# CR78-SD.net
KiCad netlist of a schematic drawn in EAGLE
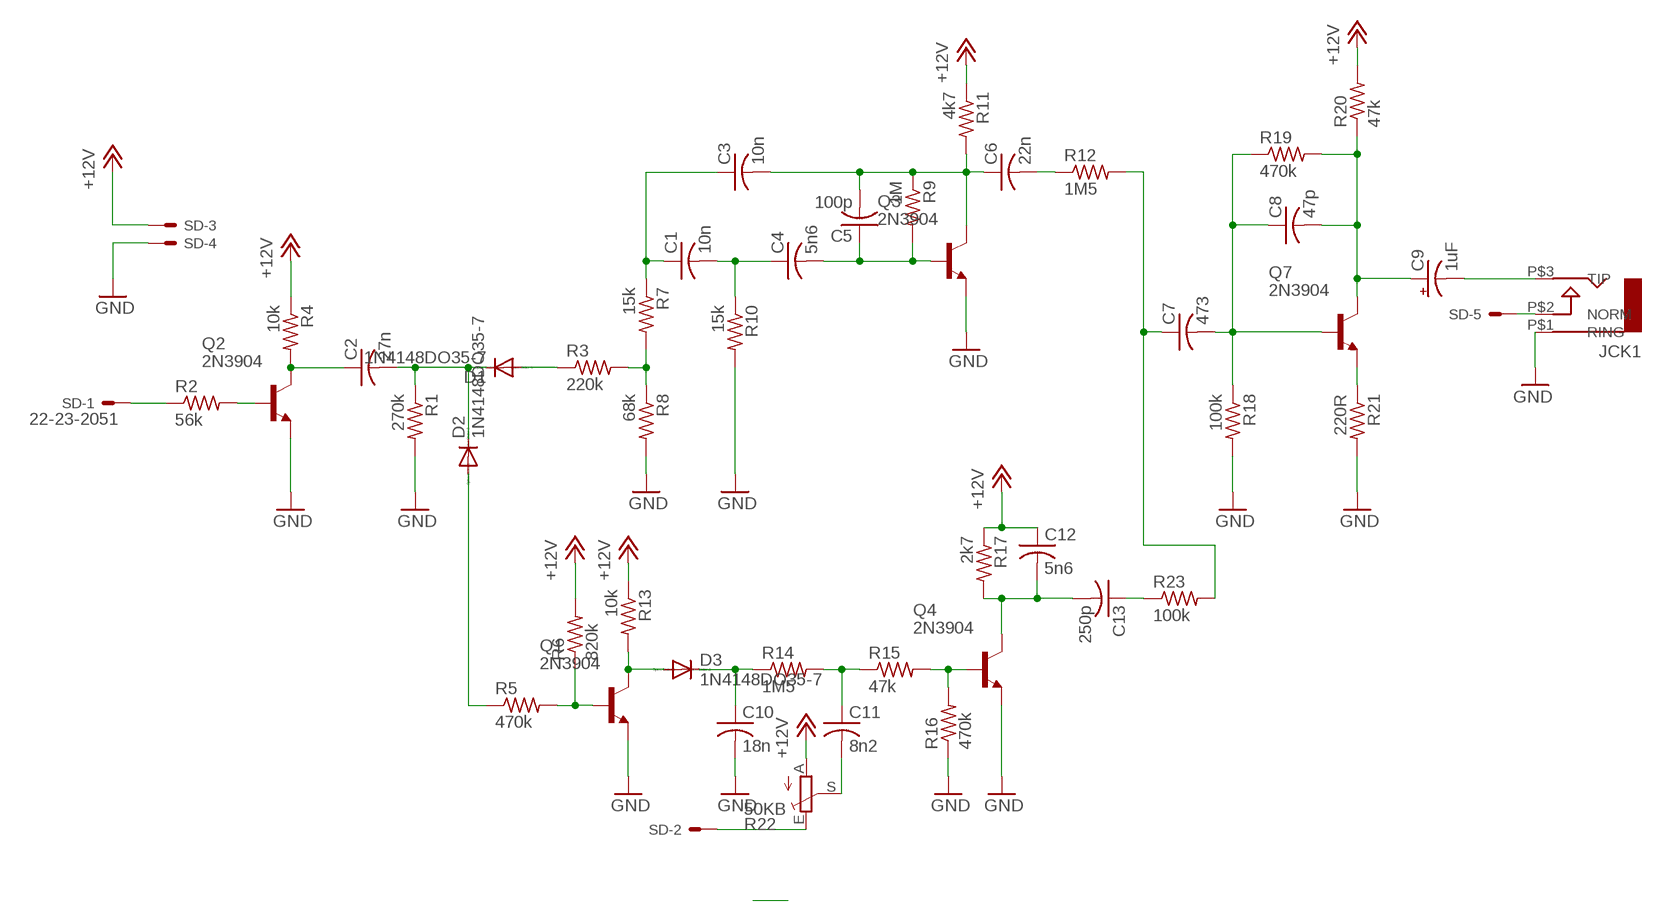
[diagram p0: schematic, sheet 1]

(export (version "E")
  (design (tool "Eeschema 10.0.6"))
  (components
    (comp (ref "C1")
      (value "10n")
      (footprint "eagle-import:C050-025X075")
      (libsource (lib "eagle-import") (part "C-US050-025X075"))
    )
    (comp (ref "C2")
      (value "27n")
      (footprint "eagle-import:C050-025X075")
      (libsource (lib "eagle-import") (part "C-US050-025X075"))
    )
    (comp (ref "C3")
      (value "10n")
      (footprint "eagle-import:C050-025X075")
      (libsource (lib "eagle-import") (part "C-US050-025X075"))
    )
    (comp (ref "C4")
      (value "5n6")
      (footprint "eagle-import:C050-025X075")
      (libsource (lib "eagle-import") (part "C-US050-025X075"))
    )
    (comp (ref "C5")
      (value "100p")
      (footprint "eagle-import:C050-025X075")
      (libsource (lib "eagle-import") (part "C-US050-025X075"))
    )
    (comp (ref "C6")
      (value "22n")
      (footprint "eagle-import:C050-025X075")
      (libsource (lib "eagle-import") (part "C-US050-025X075"))
    )
    (comp (ref "C7")
      (value "473")
      (footprint "eagle-import:C050-025X075")
      (libsource (lib "eagle-import") (part "C-US050-025X075"))
    )
    (comp (ref "C8")
      (value "47p")
      (footprint "eagle-import:C050-025X075")
      (libsource (lib "eagle-import") (part "C-US050-025X075"))
    )
    (comp (ref "C9")
      (value "1uF")
      (footprint "eagle-import:B45181B")
      (libsource (lib "eagle-import") (part "CPOL-USB45181B"))
    )
    (comp (ref "C10")
      (value "18n")
      (footprint "eagle-import:C050-025X075")
      (libsource (lib "eagle-import") (part "C-US050-025X075"))
    )
    (comp (ref "C11")
      (value "8n2")
      (footprint "eagle-import:C050-025X075")
      (libsource (lib "eagle-import") (part "C-US050-025X075"))
    )
    (comp (ref "C12")
      (value "5n6")
      (footprint "eagle-import:C050-025X075")
      (libsource (lib "eagle-import") (part "C-US050-025X075"))
    )
    (comp (ref "C13")
      (value "250p")
      (footprint "eagle-import:C050-025X075")
      (libsource (lib "eagle-import") (part "C-US050-025X075"))
    )
    (comp (ref "D1")
      (value "1N4148DO35-7")
      (footprint "eagle-import:DO35-7")
      (libsource (lib "eagle-import") (part "1N4148DO35-7"))
    )
    (comp (ref "D2")
      (value "1N4148DO35-7")
      (footprint "eagle-import:DO35-7")
      (libsource (lib "eagle-import") (part "1N4148DO35-7"))
    )
    (comp (ref "D3")
      (value "1N4148DO35-7")
      (footprint "eagle-import:DO35-7")
      (libsource (lib "eagle-import") (part "1N4148DO35-7"))
    )
    (comp (ref "JCK1")
      (value "AUDIO-JACK")
      (footprint "eagle-import:ERTHENVAR-JACK-90DEG")
      (libsource (lib "eagle-import") (part "AUDIO-JACK"))
    )
    (comp (ref "Q1")
      (value "2N3904")
      (footprint "eagle-import:TO92")
      (libsource (lib "eagle-import") (part "2N3904"))
    )
    (comp (ref "Q2")
      (value "2N3904")
      (footprint "eagle-import:TO92")
      (libsource (lib "eagle-import") (part "2N3904"))
    )
    (comp (ref "Q3")
      (value "2N3904")
      (footprint "eagle-import:TO92")
      (libsource (lib "eagle-import") (part "2N3904"))
    )
    (comp (ref "Q4")
      (value "2N3904")
      (footprint "eagle-import:TO92")
      (libsource (lib "eagle-import") (part "2N3904"))
    )
    (comp (ref "Q7")
      (value "2N3904")
      (footprint "eagle-import:TO92")
      (libsource (lib "eagle-import") (part "2N3904"))
    )
    (comp (ref "R1")
      (value "270k")
      (footprint "eagle-import:0207_7")
      (libsource (lib "eagle-import") (part "R-US_0207/7"))
    )
    (comp (ref "R2")
      (value "56k")
      (footprint "eagle-import:0207_7")
      (libsource (lib "eagle-import") (part "R-US_0207/7"))
    )
    (comp (ref "R3")
      (value "220k")
      (footprint "eagle-import:0207_7")
      (libsource (lib "eagle-import") (part "R-US_0207/7"))
    )
    (comp (ref "R4")
      (value "10k")
      (footprint "eagle-import:0207_7")
      (libsource (lib "eagle-import") (part "R-US_0207/7"))
    )
    (comp (ref "R5")
      (value "470k")
      (footprint "eagle-import:0207_7")
      (libsource (lib "eagle-import") (part "R-US_0207/7"))
    )
    (comp (ref "R6")
      (value "820k")
      (footprint "eagle-import:0207_7")
      (libsource (lib "eagle-import") (part "R-US_0207/7"))
    )
    (comp (ref "R7")
      (value "15k")
      (footprint "eagle-import:0207_7")
      (libsource (lib "eagle-import") (part "R-US_0207/7"))
    )
    (comp (ref "R8")
      (value "68k")
      (footprint "eagle-import:0207_7")
      (libsource (lib "eagle-import") (part "R-US_0207/7"))
    )
    (comp (ref "R9")
      (value "1M")
      (footprint "eagle-import:0207_7")
      (libsource (lib "eagle-import") (part "R-US_0207/7"))
    )
    (comp (ref "R10")
      (value "15k")
      (footprint "eagle-import:0207_7")
      (libsource (lib "eagle-import") (part "R-US_0207/7"))
    )
    (comp (ref "R11")
      (value "4k7")
      (footprint "eagle-import:0207_7")
      (libsource (lib "eagle-import") (part "R-US_0207/7"))
    )
    (comp (ref "R12")
      (value "1M5")
      (footprint "eagle-import:0207_7")
      (libsource (lib "eagle-import") (part "R-US_0207/7"))
    )
    (comp (ref "R13")
      (value "10k")
      (footprint "eagle-import:0207_7")
      (libsource (lib "eagle-import") (part "R-US_0207/7"))
    )
    (comp (ref "R14")
      (value "1M5")
      (footprint "eagle-import:0207_7")
      (libsource (lib "eagle-import") (part "R-US_0207/7"))
    )
    (comp (ref "R15")
      (value "47k")
      (footprint "eagle-import:0207_7")
      (libsource (lib "eagle-import") (part "R-US_0207/7"))
    )
    (comp (ref "R16")
      (value "470k")
      (footprint "eagle-import:0207_7")
      (libsource (lib "eagle-import") (part "R-US_0207/7"))
    )
    (comp (ref "R17")
      (value "2k7")
      (footprint "eagle-import:0207_7")
      (libsource (lib "eagle-import") (part "R-US_0207/7"))
    )
    (comp (ref "R18")
      (value "100k")
      (footprint "eagle-import:0207_7")
      (libsource (lib "eagle-import") (part "R-US_0207/7"))
    )
    (comp (ref "R19")
      (value "470k")
      (footprint "eagle-import:0207_7")
      (libsource (lib "eagle-import") (part "R-US_0207/7"))
    )
    (comp (ref "R20")
      (value "47k")
      (footprint "eagle-import:0207_7")
      (libsource (lib "eagle-import") (part "R-US_0207/7"))
    )
    (comp (ref "R21")
      (value "220R")
      (footprint "eagle-import:0207_7")
      (libsource (lib "eagle-import") (part "R-US_0207/7"))
    )
    (comp (ref "R22")
      (value "50KB")
      (footprint "eagle-import:B64Y")
      (libsource (lib "eagle-import") (part "TRIM_EU-B64Y"))
    )
    (comp (ref "R23")
      (value "100k")
      (footprint "eagle-import:0207_7")
      (libsource (lib "eagle-import") (part "R-US_0207/7"))
    )
    (comp (ref "SD")
      (value "22-23-2051")
      (footprint "eagle-import:22-23-2051")
      (fields (field (name "MF") "MOLEX"))
      (libsource (lib "eagle-import") (part "22-23-2051"))
    )
  )
  (nets
    (net (code "1") (name "+12V") (class "Default")
      (node (ref "C12") (pin "1") (pinfunction "1_1") (pintype "passive"))
      (node (ref "R11") (pin "1") (pinfunction "1_1") (pintype "passive"))
      (node (ref "R13") (pin "1") (pinfunction "1_1") (pintype "passive"))
      (node (ref "R17") (pin "1") (pinfunction "1_1") (pintype "passive"))
      (node (ref "R20") (pin "2") (pinfunction "2_2") (pintype "passive"))
      (node (ref "R22") (pin "A") (pinfunction "A_A") (pintype "passive"))
      (node (ref "R4") (pin "1") (pinfunction "1_1") (pintype "passive"))
      (node (ref "R6") (pin "2") (pinfunction "2_2") (pintype "passive"))
      (node (ref "SD") (pin "3") (pinfunction "S_3") (pintype "passive"))
    )
    (net (code "2") (name "GND") (class "Default")
      (node (ref "C10") (pin "2") (pinfunction "2_2") (pintype "passive"))
      (node (ref "JCK1") (pin "P$1") (pinfunction "RING_P$1") (pintype "bidirectional"))
      (node (ref "Q1") (pin "3") (pinfunction "E_3") (pintype "passive"))
      (node (ref "Q2") (pin "3") (pinfunction "E_3") (pintype "passive"))
      (node (ref "Q3") (pin "3") (pinfunction "E_3") (pintype "passive"))
      (node (ref "Q4") (pin "3") (pinfunction "E_3") (pintype "passive"))
      (node (ref "R1") (pin "2") (pinfunction "2_2") (pintype "passive"))
      (node (ref "R10") (pin "2") (pinfunction "2_2") (pintype "passive"))
      (node (ref "R16") (pin "1") (pinfunction "1_1") (pintype "passive"))
      (node (ref "R18") (pin "2") (pinfunction "2_2") (pintype "passive"))
      (node (ref "R21") (pin "2") (pinfunction "2_2") (pintype "passive"))
      (node (ref "R8") (pin "2") (pinfunction "2_2") (pintype "passive"))
      (node (ref "SD") (pin "4") (pinfunction "S_4") (pintype "passive"))
    )
    (net (code "3") (name "Net-(C1-Pad1)") (class "Default")
      (node (ref "C1") (pin "1") (pinfunction "1_1") (pintype "passive"))
      (node (ref "C3") (pin "1") (pinfunction "1_1") (pintype "passive"))
      (node (ref "R7") (pin "1") (pinfunction "1_1") (pintype "passive"))
    )
    (net (code "4") (name "Net-(C1-Pad2)") (class "Default")
      (node (ref "C1") (pin "2") (pinfunction "2_2") (pintype "passive"))
      (node (ref "C4") (pin "1") (pinfunction "1_1") (pintype "passive"))
      (node (ref "R10") (pin "1") (pinfunction "1_1") (pintype "passive"))
    )
    (net (code "5") (name "Net-(C2-Pad2)") (class "Default")
      (node (ref "C2") (pin "2") (pinfunction "2_2") (pintype "passive"))
      (node (ref "D1") (pin "C") (pinfunction "C_C") (pintype "passive"))
      (node (ref "D2") (pin "C") (pinfunction "C_C") (pintype "passive"))
      (node (ref "R1") (pin "1") (pinfunction "1_1") (pintype "passive"))
    )
    (net (code "6") (name "Net-(C6-Pad2)") (class "Default")
      (node (ref "C6") (pin "2") (pinfunction "2_2") (pintype "passive"))
      (node (ref "R12") (pin "1") (pinfunction "1_1") (pintype "passive"))
    )
    (net (code "7") (name "Net-(C7-Pad1)") (class "Default")
      (node (ref "C7") (pin "1") (pinfunction "1_1") (pintype "passive"))
      (node (ref "R12") (pin "2") (pinfunction "2_2") (pintype "passive"))
      (node (ref "R23") (pin "2") (pinfunction "2_2") (pintype "passive"))
    )
    (net (code "8") (name "Net-(C10-Pad1)") (class "Default")
      (node (ref "C10") (pin "1") (pinfunction "1_1") (pintype "passive"))
      (node (ref "D3") (pin "C") (pinfunction "C_C") (pintype "passive"))
      (node (ref "R14") (pin "1") (pinfunction "1_1") (pintype "passive"))
    )
    (net (code "9") (name "Net-(C11-Pad1)") (class "Default")
      (node (ref "C11") (pin "1") (pinfunction "1_1") (pintype "passive"))
      (node (ref "R14") (pin "2") (pinfunction "2_2") (pintype "passive"))
      (node (ref "R15") (pin "1") (pinfunction "1_1") (pintype "passive"))
    )
    (net (code "10") (name "Net-(C11-Pad2)") (class "Default")
      (node (ref "C11") (pin "2") (pinfunction "2_2") (pintype "passive"))
      (node (ref "R22") (pin "S") (pinfunction "S_S") (pintype "passive"))
    )
    (net (code "11") (name "Net-(C13-Pad1)") (class "Default")
      (node (ref "C13") (pin "1") (pinfunction "1_1") (pintype "passive"))
      (node (ref "R23") (pin "1") (pinfunction "1_1") (pintype "passive"))
    )
    (net (code "12") (name "Net-(D1-PadA)") (class "Default")
      (node (ref "D1") (pin "A") (pinfunction "A_A") (pintype "passive"))
      (node (ref "R3") (pin "1") (pinfunction "1_1") (pintype "passive"))
    )
    (net (code "13") (name "Net-(D2-PadA)") (class "Default")
      (node (ref "D2") (pin "A") (pinfunction "A_A") (pintype "passive"))
      (node (ref "R5") (pin "1") (pinfunction "1_1") (pintype "passive"))
    )
    (net (code "14") (name "Net-(JCK1-NORM)") (class "Default")
      (node (ref "JCK1") (pin "P$2") (pinfunction "NORM_P$2") (pintype "bidirectional"))
      (node (ref "SD") (pin "5") (pinfunction "S_5") (pintype "passive"))
    )
    (net (code "15") (name "Net-(JCK1-TIP)") (class "Default")
      (node (ref "C9") (pin "-") (pinfunction "-_-") (pintype "passive"))
      (node (ref "JCK1") (pin "P$3") (pinfunction "TIP_P$3") (pintype "bidirectional"))
    )
    (net (code "16") (name "Net-(Q1-B)") (class "Default")
      (node (ref "Q1") (pin "2") (pinfunction "B_2") (pintype "passive"))
      (node (ref "R5") (pin "2") (pinfunction "2_2") (pintype "passive"))
      (node (ref "R6") (pin "1") (pinfunction "1_1") (pintype "passive"))
    )
    (net (code "17") (name "Net-(Q1-C)") (class "Default")
      (node (ref "D3") (pin "A") (pinfunction "A_A") (pintype "passive"))
      (node (ref "Q1") (pin "1") (pinfunction "C_1") (pintype "passive"))
      (node (ref "R13") (pin "2") (pinfunction "2_2") (pintype "passive"))
    )
    (net (code "18") (name "Net-(Q2-B)") (class "Default")
      (node (ref "Q2") (pin "2") (pinfunction "B_2") (pintype "passive"))
      (node (ref "R2") (pin "2") (pinfunction "2_2") (pintype "passive"))
    )
    (net (code "19") (name "Net-(Q2-C)") (class "Default")
      (node (ref "C2") (pin "1") (pinfunction "1_1") (pintype "passive"))
      (node (ref "Q2") (pin "1") (pinfunction "C_1") (pintype "passive"))
      (node (ref "R4") (pin "2") (pinfunction "2_2") (pintype "passive"))
    )
    (net (code "20") (name "Net-(Q3-B)") (class "Default")
      (node (ref "C4") (pin "2") (pinfunction "2_2") (pintype "passive"))
      (node (ref "C5") (pin "1") (pinfunction "1_1") (pintype "passive"))
      (node (ref "Q3") (pin "2") (pinfunction "B_2") (pintype "passive"))
      (node (ref "R9") (pin "2") (pinfunction "2_2") (pintype "passive"))
    )
    (net (code "21") (name "Net-(Q3-C)") (class "Default")
      (node (ref "C3") (pin "2") (pinfunction "2_2") (pintype "passive"))
      (node (ref "C5") (pin "2") (pinfunction "2_2") (pintype "passive"))
      (node (ref "C6") (pin "1") (pinfunction "1_1") (pintype "passive"))
      (node (ref "Q3") (pin "1") (pinfunction "C_1") (pintype "passive"))
      (node (ref "R11") (pin "2") (pinfunction "2_2") (pintype "passive"))
      (node (ref "R9") (pin "1") (pinfunction "1_1") (pintype "passive"))
    )
    (net (code "22") (name "Net-(Q4-B)") (class "Default")
      (node (ref "Q4") (pin "2") (pinfunction "B_2") (pintype "passive"))
      (node (ref "R15") (pin "2") (pinfunction "2_2") (pintype "passive"))
      (node (ref "R16") (pin "2") (pinfunction "2_2") (pintype "passive"))
    )
    (net (code "23") (name "Net-(Q4-C)") (class "Default")
      (node (ref "C12") (pin "2") (pinfunction "2_2") (pintype "passive"))
      (node (ref "C13") (pin "2") (pinfunction "2_2") (pintype "passive"))
      (node (ref "Q4") (pin "1") (pinfunction "C_1") (pintype "passive"))
      (node (ref "R17") (pin "2") (pinfunction "2_2") (pintype "passive"))
    )
    (net (code "24") (name "Net-(Q7-B)") (class "Default")
      (node (ref "C7") (pin "2") (pinfunction "2_2") (pintype "passive"))
      (node (ref "C8") (pin "1") (pinfunction "1_1") (pintype "passive"))
      (node (ref "Q7") (pin "2") (pinfunction "B_2") (pintype "passive"))
      (node (ref "R18") (pin "1") (pinfunction "1_1") (pintype "passive"))
      (node (ref "R19") (pin "1") (pinfunction "1_1") (pintype "passive"))
    )
    (net (code "25") (name "Net-(Q7-C)") (class "Default")
      (node (ref "C8") (pin "2") (pinfunction "2_2") (pintype "passive"))
      (node (ref "C9") (pin "+") (pinfunction "+_+") (pintype "passive"))
      (node (ref "Q7") (pin "1") (pinfunction "C_1") (pintype "passive"))
      (node (ref "R19") (pin "2") (pinfunction "2_2") (pintype "passive"))
      (node (ref "R20") (pin "1") (pinfunction "1_1") (pintype "passive"))
    )
    (net (code "26") (name "Net-(Q7-E)") (class "Default")
      (node (ref "Q7") (pin "3") (pinfunction "E_3") (pintype "passive"))
      (node (ref "R21") (pin "1") (pinfunction "1_1") (pintype "passive"))
    )
    (net (code "27") (name "Net-(R3-Pad2)") (class "Default")
      (node (ref "R3") (pin "2") (pinfunction "2_2") (pintype "passive"))
      (node (ref "R7") (pin "2") (pinfunction "2_2") (pintype "passive"))
      (node (ref "R8") (pin "1") (pinfunction "1_1") (pintype "passive"))
    )
    (net (code "28") (name "Net-(SDA-S)") (class "Default")
      (node (ref "R2") (pin "1") (pinfunction "1_1") (pintype "passive"))
      (node (ref "SD") (pin "1") (pinfunction "S_1") (pintype "passive"))
    )
    (net (code "29") (name "Net-(SDB-S)") (class "Default")
      (node (ref "R22") (pin "E") (pinfunction "E_E") (pintype "passive"))
      (node (ref "SD") (pin "2") (pinfunction "S_2") (pintype "passive"))
    )
  )
)
